# battery-board.net
KiCad netlist of a schematic drawn in EAGLE
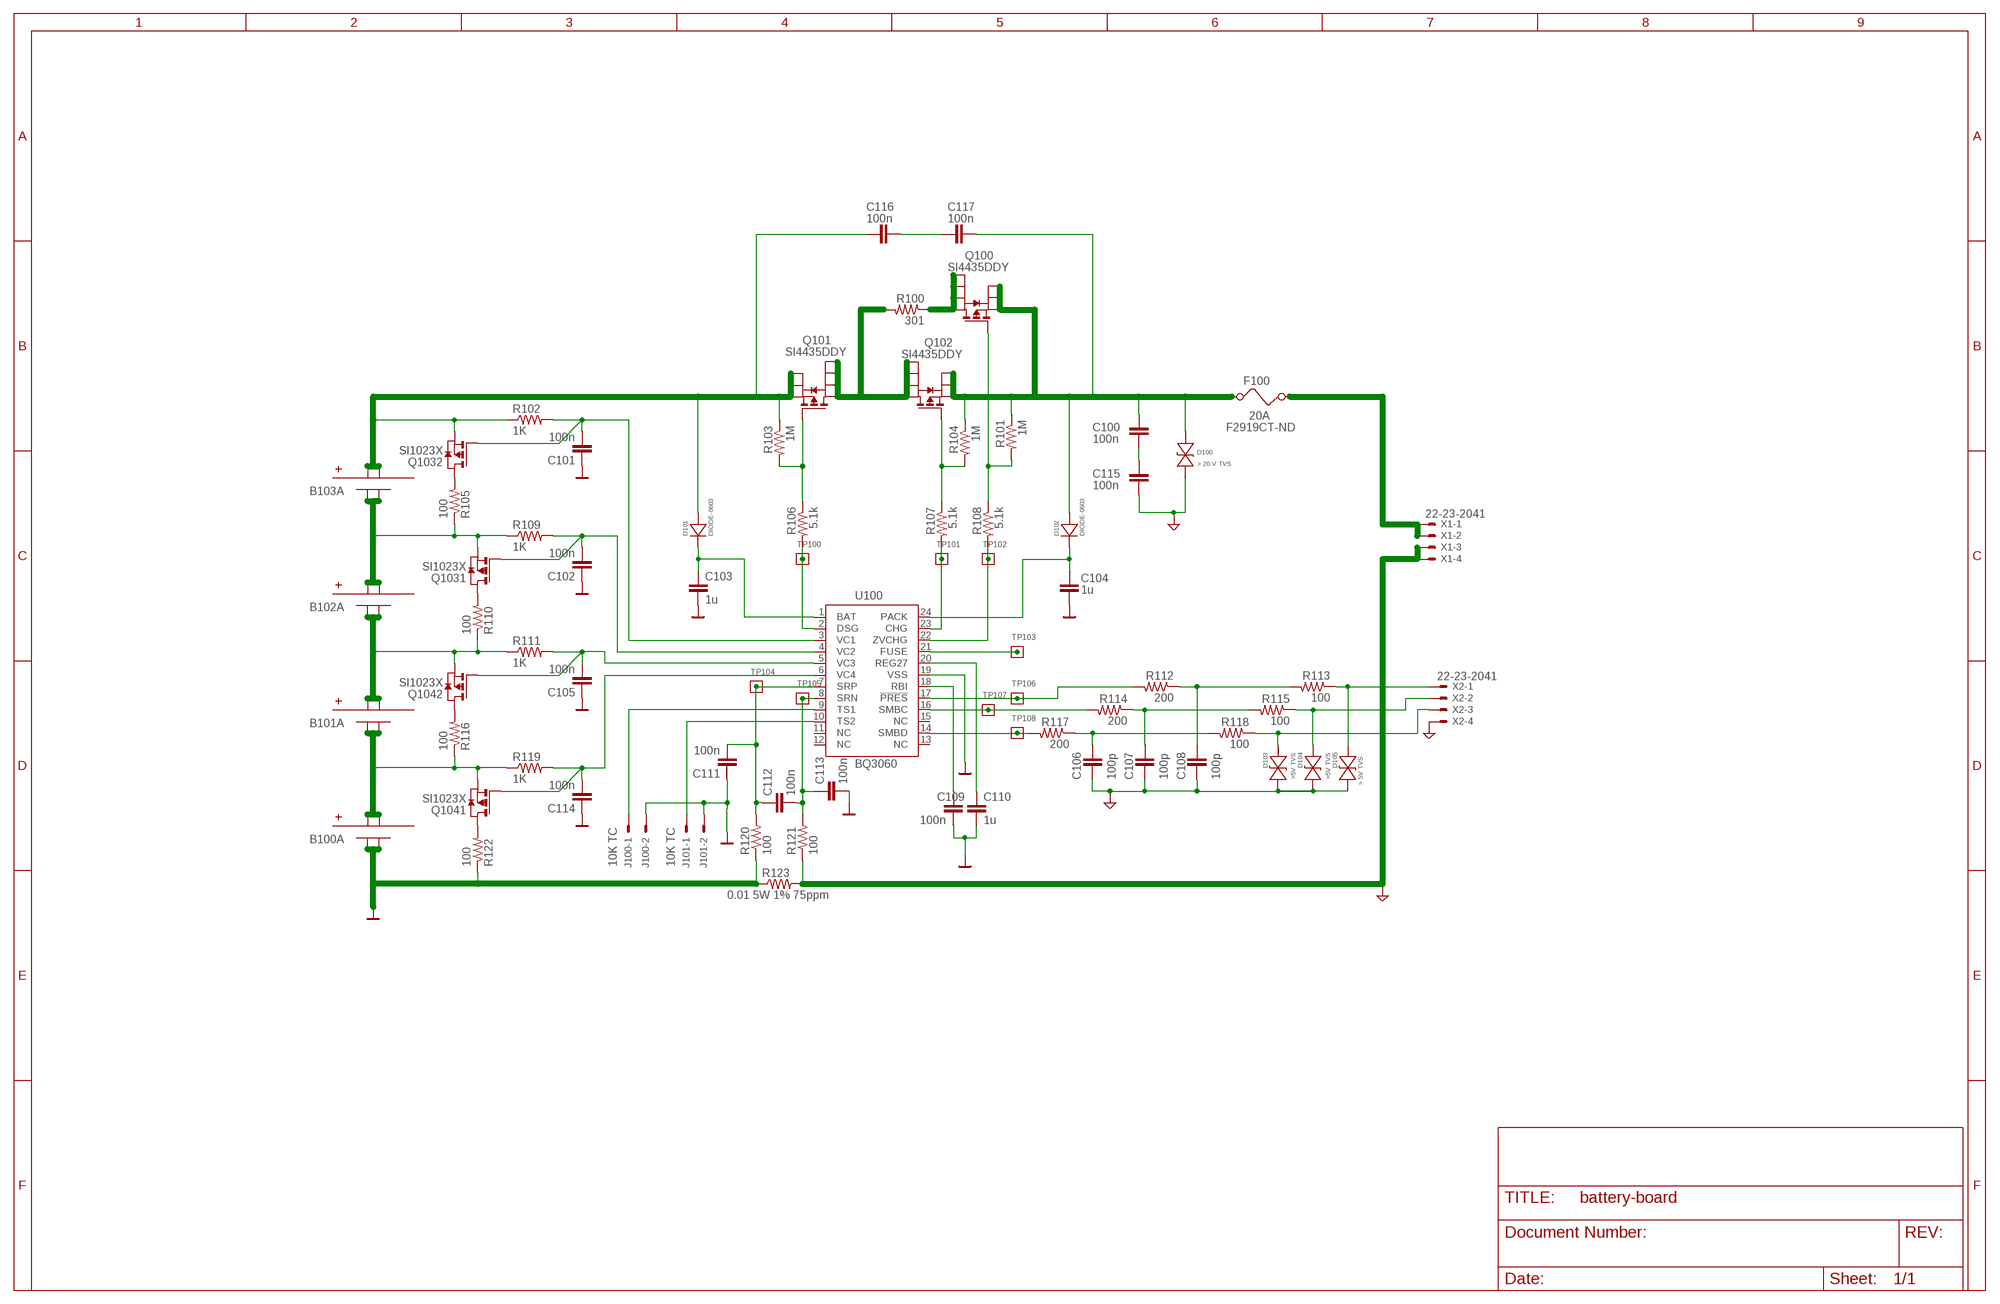
[diagram p0: schematic, sheet 1]

(export (version "E")
  (design (tool "Eeschema 10.0.6"))
  (components
    (comp (ref "B100A")
      (value "LIPO-8AHR")
      (footprint "eagle-import:LIPO-8AHR-PAC")
      (libsource (lib "eagle-import") (part "LIPO-8AHR"))
    )
    (comp (ref "B101A")
      (value "LIPO-8AHR")
      (footprint "eagle-import:LIPO-8AHR-PAC")
      (libsource (lib "eagle-import") (part "LIPO-8AHR"))
    )
    (comp (ref "B102A")
      (value "LIPO-8AHR")
      (footprint "eagle-import:LIPO-8AHR-PAC")
      (libsource (lib "eagle-import") (part "LIPO-8AHR"))
    )
    (comp (ref "B103A")
      (value "LIPO-8AHR")
      (footprint "eagle-import:LIPO-8AHR-PAC")
      (libsource (lib "eagle-import") (part "LIPO-8AHR"))
    )
    (comp (ref "C100")
      (value "100n")
      (footprint "eagle-import:0603-B-NOSILK")
      (libsource (lib "eagle-import") (part "C-EU0603-B-NOSILK"))
    )
    (comp (ref "C101")
      (value "100n")
      (footprint "eagle-import:0603-B-NOSILK")
      (libsource (lib "eagle-import") (part "C-EU0603-B-NOSILK"))
    )
    (comp (ref "C102")
      (value "100n")
      (footprint "eagle-import:0603-B-NOSILK")
      (libsource (lib "eagle-import") (part "C-EU0603-B-NOSILK"))
    )
    (comp (ref "C103")
      (value "1u")
      (footprint "eagle-import:0603-B-NOSILK")
      (libsource (lib "eagle-import") (part "C-EU0603-B-NOSILK"))
    )
    (comp (ref "C104")
      (value "1u")
      (footprint "eagle-import:0603-B-NOSILK")
      (libsource (lib "eagle-import") (part "C-EU0603-B-NOSILK"))
    )
    (comp (ref "C105")
      (value "100n")
      (footprint "eagle-import:0603-B-NOSILK")
      (libsource (lib "eagle-import") (part "C-EU0603-B-NOSILK"))
    )
    (comp (ref "C106")
      (value "100p")
      (footprint "eagle-import:0603-B-NOSILK")
      (libsource (lib "eagle-import") (part "C-EU0603-B-NOSILK"))
    )
    (comp (ref "C107")
      (value "100p")
      (footprint "eagle-import:0603-B-NOSILK")
      (libsource (lib "eagle-import") (part "C-EU0603-B-NOSILK"))
    )
    (comp (ref "C108")
      (value "100p")
      (footprint "eagle-import:0603-B-NOSILK")
      (libsource (lib "eagle-import") (part "C-EU0603-B-NOSILK"))
    )
    (comp (ref "C109")
      (value "100n")
      (footprint "eagle-import:0603-B-NOSILK")
      (libsource (lib "eagle-import") (part "C-EU0603-B-NOSILK"))
    )
    (comp (ref "C110")
      (value "1u")
      (footprint "eagle-import:0603-B-NOSILK")
      (libsource (lib "eagle-import") (part "C-EU0603-B-NOSILK"))
    )
    (comp (ref "C111")
      (value "100n")
      (footprint "eagle-import:0603-B-NOSILK")
      (libsource (lib "eagle-import") (part "C-EU0603-B-NOSILK"))
    )
    (comp (ref "C112")
      (value "100n")
      (footprint "eagle-import:0603-B-NOSILK")
      (libsource (lib "eagle-import") (part "C-EU0603-B-NOSILK"))
    )
    (comp (ref "C113")
      (value "100n")
      (footprint "eagle-import:0603-B-NOSILK")
      (libsource (lib "eagle-import") (part "C-EU0603-B-NOSILK"))
    )
    (comp (ref "C114")
      (value "100n")
      (footprint "eagle-import:0603-B-NOSILK")
      (libsource (lib "eagle-import") (part "C-EU0603-B-NOSILK"))
    )
    (comp (ref "C115")
      (value "100n")
      (footprint "eagle-import:0603-B-NOSILK")
      (libsource (lib "eagle-import") (part "C-EU0603-B-NOSILK"))
    )
    (comp (ref "C116")
      (value "100n")
      (footprint "eagle-import:0603-B-NOSILK")
      (libsource (lib "eagle-import") (part "C-EU0603-B-NOSILK"))
    )
    (comp (ref "C117")
      (value "100n")
      (footprint "eagle-import:0603-B-NOSILK")
      (libsource (lib "eagle-import") (part "C-EU0603-B-NOSILK"))
    )
    (comp (ref "D100")
      (value "> 20 V TVS")
      (footprint "eagle-import:0603-B-NOSILK-DIODE")
      (libsource (lib "eagle-import") (part "TVS-0603"))
    )
    (comp (ref "D101")
      (value "DIODE-0603")
      (footprint "eagle-import:0603-B-NOSILK-DIODE")
      (libsource (lib "eagle-import") (part "DIODE-0603"))
    )
    (comp (ref "D102")
      (value "DIODE-0603")
      (footprint "eagle-import:0603-B-NOSILK-DIODE")
      (libsource (lib "eagle-import") (part "DIODE-0603"))
    )
    (comp (ref "D103")
      (value ">5V TVS")
      (footprint "eagle-import:0603-B-NOSILK-DIODE")
      (libsource (lib "eagle-import") (part "TVS-0603"))
    )
    (comp (ref "D104")
      (value ">5V TVS")
      (footprint "eagle-import:0603-B-NOSILK-DIODE")
      (libsource (lib "eagle-import") (part "TVS-0603"))
    )
    (comp (ref "D105")
      (value "> 5V TVS")
      (footprint "eagle-import:0603-B-NOSILK-DIODE")
      (libsource (lib "eagle-import") (part "TVS-0603"))
    )
    (comp (ref "F100")
      (value "20A")
      (footprint "eagle-import:1206")
      (fields (field (name "DK") "F2919CT-ND"))
      (libsource (lib "eagle-import") (part "FUSE1206"))
    )
    (comp (ref "J100")
      (value "87758-0216")
      (footprint "eagle-import:87758-0216")
      (libsource (lib "eagle-import") (part "87758-0216"))
    )
    (comp (ref "J101")
      (value "87758-0216")
      (footprint "eagle-import:87758-0216")
      (libsource (lib "eagle-import") (part "87758-0216"))
    )
    (comp (ref "Q100")
      (value "SI4435DDY")
      (footprint "eagle-import:SO-8")
      (libsource (lib "eagle-import") (part "SI4435DDY"))
    )
    (comp (ref "Q101")
      (value "SI4435DDY")
      (footprint "eagle-import:SO-8")
      (libsource (lib "eagle-import") (part "SI4435DDY"))
    )
    (comp (ref "Q102")
      (value "SI4435DDY")
      (footprint "eagle-import:SO-8")
      (libsource (lib "eagle-import") (part "SI4435DDY"))
    )
    (comp (ref "Q103")
      (value "SI1023X")
      (footprint "eagle-import:SOT-563")
      (libsource (lib "eagle-import") (part "SI1023X"))
    )
    (comp (ref "Q104")
      (value "SI1023X")
      (footprint "eagle-import:SOT-563")
      (libsource (lib "eagle-import") (part "SI1023X"))
    )
    (comp (ref "R100")
      (value "301")
      (footprint "eagle-import:1206-B")
      (libsource (lib "eagle-import") (part "R-US_1206-B"))
    )
    (comp (ref "R101")
      (value "1M")
      (footprint "eagle-import:0603-B-NOSILK")
      (libsource (lib "eagle-import") (part "R-US_0603-B-NOSILK"))
    )
    (comp (ref "R102")
      (value "1K")
      (footprint "eagle-import:0603-B-NOSILK")
      (libsource (lib "eagle-import") (part "R-US_0603-B-NOSILK"))
    )
    (comp (ref "R103")
      (value "1M")
      (footprint "eagle-import:0603-B-NOSILK")
      (libsource (lib "eagle-import") (part "R-US_0603-B-NOSILK"))
    )
    (comp (ref "R104")
      (value "1M")
      (footprint "eagle-import:0603-B-NOSILK")
      (libsource (lib "eagle-import") (part "R-US_0603-B-NOSILK"))
    )
    (comp (ref "R105")
      (value "100")
      (footprint "eagle-import:0603-B-NOSILK")
      (libsource (lib "eagle-import") (part "R-US_0603-B-NOSILK"))
    )
    (comp (ref "R106")
      (value "5.1k")
      (footprint "eagle-import:0603-B-NOSILK")
      (libsource (lib "eagle-import") (part "R-US_0603-B-NOSILK"))
    )
    (comp (ref "R107")
      (value "5.1k")
      (footprint "eagle-import:0603-B-NOSILK")
      (libsource (lib "eagle-import") (part "R-US_0603-B-NOSILK"))
    )
    (comp (ref "R108")
      (value "5.1k")
      (footprint "eagle-import:0603-B-NOSILK")
      (libsource (lib "eagle-import") (part "R-US_0603-B-NOSILK"))
    )
    (comp (ref "R109")
      (value "1K")
      (footprint "eagle-import:0603-B-NOSILK")
      (libsource (lib "eagle-import") (part "R-US_0603-B-NOSILK"))
    )
    (comp (ref "R110")
      (value "100")
      (footprint "eagle-import:0603-B-NOSILK")
      (libsource (lib "eagle-import") (part "R-US_0603-B-NOSILK"))
    )
    (comp (ref "R111")
      (value "1K")
      (footprint "eagle-import:0603-B-NOSILK")
      (libsource (lib "eagle-import") (part "R-US_0603-B-NOSILK"))
    )
    (comp (ref "R112")
      (value "200")
      (footprint "eagle-import:0603-B-NOSILK")
      (libsource (lib "eagle-import") (part "R-US_0603-B-NOSILK"))
    )
    (comp (ref "R113")
      (value "100")
      (footprint "eagle-import:0603-B-NOSILK")
      (libsource (lib "eagle-import") (part "R-US_0603-B-NOSILK"))
    )
    (comp (ref "R114")
      (value "200")
      (footprint "eagle-import:0603-B-NOSILK")
      (libsource (lib "eagle-import") (part "R-US_0603-B-NOSILK"))
    )
    (comp (ref "R115")
      (value "100")
      (footprint "eagle-import:0603-B-NOSILK")
      (libsource (lib "eagle-import") (part "R-US_0603-B-NOSILK"))
    )
    (comp (ref "R116")
      (value "100")
      (footprint "eagle-import:0603-B-NOSILK")
      (libsource (lib "eagle-import") (part "R-US_0603-B-NOSILK"))
    )
    (comp (ref "R117")
      (value "200")
      (footprint "eagle-import:0603-B-NOSILK")
      (libsource (lib "eagle-import") (part "R-US_0603-B-NOSILK"))
    )
    (comp (ref "R118")
      (value "100")
      (footprint "eagle-import:0603-B-NOSILK")
      (libsource (lib "eagle-import") (part "R-US_0603-B-NOSILK"))
    )
    (comp (ref "R119")
      (value "1K")
      (footprint "eagle-import:0603-B-NOSILK")
      (libsource (lib "eagle-import") (part "R-US_0603-B-NOSILK"))
    )
    (comp (ref "R120")
      (value "100")
      (footprint "eagle-import:0603-B-NOSILK")
      (libsource (lib "eagle-import") (part "R-US_0603-B-NOSILK"))
    )
    (comp (ref "R121")
      (value "100")
      (footprint "eagle-import:0603-B-NOSILK")
      (libsource (lib "eagle-import") (part "R-US_0603-B-NOSILK"))
    )
    (comp (ref "R122")
      (value "100")
      (footprint "eagle-import:0603-B-NOSILK")
      (libsource (lib "eagle-import") (part "R-US_0603-B-NOSILK"))
    )
    (comp (ref "R123")
      (value "0.01 5W 1% 75ppm")
      (footprint "eagle-import:VISHAY-2818")
      (libsource (lib "eagle-import") (part "R-US-2818"))
    )
    (comp (ref "TP100")
      (value "TEST-POINT")
      (footprint "eagle-import:2MM-TEST-POINT")
      (libsource (lib "eagle-import") (part "TEST-POINT"))
    )
    (comp (ref "TP101")
      (value "TEST-POINT")
      (footprint "eagle-import:2MM-TEST-POINT")
      (libsource (lib "eagle-import") (part "TEST-POINT"))
    )
    (comp (ref "TP102")
      (value "TEST-POINT")
      (footprint "eagle-import:2MM-TEST-POINT")
      (libsource (lib "eagle-import") (part "TEST-POINT"))
    )
    (comp (ref "TP103")
      (value "TEST-POINT")
      (footprint "eagle-import:2MM-TEST-POINT")
      (libsource (lib "eagle-import") (part "TEST-POINT"))
    )
    (comp (ref "TP104")
      (value "TEST-POINT")
      (footprint "eagle-import:2MM-TEST-POINT")
      (libsource (lib "eagle-import") (part "TEST-POINT"))
    )
    (comp (ref "TP105")
      (value "TEST-POINT")
      (footprint "eagle-import:2MM-TEST-POINT")
      (libsource (lib "eagle-import") (part "TEST-POINT"))
    )
    (comp (ref "TP106")
      (value "TEST-POINT")
      (footprint "eagle-import:2MM-TEST-POINT")
      (libsource (lib "eagle-import") (part "TEST-POINT"))
    )
    (comp (ref "TP107")
      (value "TEST-POINT")
      (footprint "eagle-import:2MM-TEST-POINT")
      (libsource (lib "eagle-import") (part "TEST-POINT"))
    )
    (comp (ref "TP108")
      (value "TEST-POINT")
      (footprint "eagle-import:2MM-TEST-POINT")
      (libsource (lib "eagle-import") (part "TEST-POINT"))
    )
    (comp (ref "U100")
      (value "BQ3060PW")
      (footprint "eagle-import:PW-R-PDSO-G24")
      (libsource (lib "eagle-import") (part "BQ3060PW"))
    )
    (comp (ref "X1")
      (value "22-23-2041")
      (footprint "eagle-import:22-23-2041")
      (fields (field (name "MF") "MOLEX"))
      (libsource (lib "eagle-import") (part "22-23-2041"))
    )
    (comp (ref "X2")
      (value "22-23-2041")
      (footprint "eagle-import:22-23-2041")
      (fields (field (name "MF") "MOLEX"))
      (libsource (lib "eagle-import") (part "22-23-2041"))
    )
  )
  (nets
    (net (code "1") (name "Net-(C100-Pad1)") (class "Default")
      (node (ref "C100") (pin "1") (pinfunction "1_1") (pintype "passive"))
      (node (ref "C117") (pin "2") (pinfunction "2_2") (pintype "passive"))
      (node (ref "D100") (pin "ANODE") (pinfunction "ANODE_ANODE") (pintype "passive"))
      (node (ref "D102") (pin "ANODE") (pinfunction "ANODE_ANODE") (pintype "passive"))
      (node (ref "F100") (pin "1") (pinfunction "1_1") (pintype "passive"))
      (node (ref "Q100") (pin "1") (pinfunction "S_1") (pintype "passive"))
      (node (ref "Q100") (pin "2") (pinfunction "S_2") (pintype "passive"))
      (node (ref "Q100") (pin "3") (pinfunction "S_3") (pintype "passive"))
      (node (ref "Q102") (pin "1") (pinfunction "S_1") (pintype "passive"))
      (node (ref "Q102") (pin "2") (pinfunction "S_2") (pintype "passive"))
      (node (ref "Q102") (pin "3") (pinfunction "S_3") (pintype "passive"))
      (node (ref "R101") (pin "1") (pinfunction "1_1") (pintype "passive"))
      (node (ref "R104") (pin "1") (pinfunction "1_1") (pintype "passive"))
    )
    (net (code "2") (name "Net-(C100-Pad2)") (class "Default")
      (node (ref "C100") (pin "2") (pinfunction "2_2") (pintype "passive"))
      (node (ref "C115") (pin "1") (pinfunction "1_1") (pintype "passive"))
    )
    (net (code "3") (name "Net-(C106-Pad1)") (class "Default")
      (node (ref "C106") (pin "1") (pinfunction "1_1") (pintype "passive"))
      (node (ref "R117") (pin "1") (pinfunction "1_1") (pintype "passive"))
      (node (ref "R118") (pin "2") (pinfunction "2_2") (pintype "passive"))
    )
    (net (code "4") (name "Net-(C107-Pad1)") (class "Default")
      (node (ref "C107") (pin "1") (pinfunction "1_1") (pintype "passive"))
      (node (ref "R114") (pin "1") (pinfunction "1_1") (pintype "passive"))
      (node (ref "R115") (pin "2") (pinfunction "2_2") (pintype "passive"))
    )
    (net (code "5") (name "Net-(C108-Pad1)") (class "Default")
      (node (ref "C108") (pin "1") (pinfunction "1_1") (pintype "passive"))
      (node (ref "R112") (pin "1") (pinfunction "1_1") (pintype "passive"))
      (node (ref "R113") (pin "2") (pinfunction "2_2") (pintype "passive"))
    )
    (net (code "6") (name "Net-(C116-Pad2)") (class "Default")
      (node (ref "C116") (pin "2") (pinfunction "2_2") (pintype "passive"))
      (node (ref "C117") (pin "1") (pinfunction "1_1") (pintype "passive"))
    )
    (net (code "7") (name "Net-(J100A-S)") (class "Default")
      (node (ref "J100") (pin "1") (pinfunction "S_1") (pintype "passive"))
      (node (ref "U100") (pin "9") (pinfunction "TS1_9") (pintype "input"))
    )
    (net (code "8") (name "Net-(J101A-S)") (class "Default")
      (node (ref "J101") (pin "1") (pinfunction "S_1") (pintype "passive"))
      (node (ref "U100") (pin "10") (pinfunction "TS2_10") (pintype "input"))
    )
    (net (code "9") (name "Net-(Q100-D-Pad5)") (class "Default")
      (node (ref "Q100") (pin "5") (pinfunction "D_5") (pintype "passive"))
      (node (ref "Q100") (pin "6") (pinfunction "D_6") (pintype "passive"))
      (node (ref "Q100") (pin "7") (pinfunction "D_7") (pintype "passive"))
      (node (ref "Q100") (pin "8") (pinfunction "D_8") (pintype "passive"))
      (node (ref "R100") (pin "1") (pinfunction "1_1") (pintype "passive"))
    )
    (net (code "10") (name "Net-(Q100-G)") (class "Default")
      (node (ref "Q100") (pin "4") (pinfunction "G_4") (pintype "passive"))
      (node (ref "R101") (pin "2") (pinfunction "2_2") (pintype "passive"))
      (node (ref "R108") (pin "1") (pinfunction "1_1") (pintype "passive"))
    )
    (net (code "11") (name "Net-(Q101-D-Pad5)") (class "Default")
      (node (ref "Q101") (pin "5") (pinfunction "D_5") (pintype "passive"))
      (node (ref "Q101") (pin "6") (pinfunction "D_6") (pintype "passive"))
      (node (ref "Q101") (pin "7") (pinfunction "D_7") (pintype "passive"))
      (node (ref "Q101") (pin "8") (pinfunction "D_8") (pintype "passive"))
      (node (ref "Q102") (pin "5") (pinfunction "D_5") (pintype "passive"))
      (node (ref "Q102") (pin "6") (pinfunction "D_6") (pintype "passive"))
      (node (ref "Q102") (pin "7") (pinfunction "D_7") (pintype "passive"))
      (node (ref "Q102") (pin "8") (pinfunction "D_8") (pintype "passive"))
      (node (ref "R100") (pin "2") (pinfunction "2_2") (pintype "passive"))
    )
    (net (code "12") (name "Net-(Q101-G)") (class "Default")
      (node (ref "Q101") (pin "4") (pinfunction "G_4") (pintype "passive"))
      (node (ref "R103") (pin "2") (pinfunction "2_2") (pintype "passive"))
      (node (ref "R106") (pin "1") (pinfunction "1_1") (pintype "passive"))
    )
    (net (code "13") (name "Net-(Q102-G)") (class "Default")
      (node (ref "Q102") (pin "4") (pinfunction "G_4") (pintype "passive"))
      (node (ref "R104") (pin "2") (pinfunction "2_2") (pintype "passive"))
      (node (ref "R107") (pin "1") (pinfunction "1_1") (pintype "passive"))
    )
    (net (code "14") (name "Net-(Q103A-D)") (class "Default")
      (node (ref "Q103") (pin "6") (pinfunction "D_6") (pintype "passive"))
      (node (ref "R110") (pin "2") (pinfunction "2_2") (pintype "passive"))
    )
    (net (code "15") (name "Net-(Q103A-G)") (class "Default")
      (node (ref "C102") (pin "2") (pinfunction "2_2") (pintype "passive"))
      (node (ref "Q103") (pin "2") (pinfunction "G_2") (pintype "passive"))
      (node (ref "R109") (pin "2") (pinfunction "2_2") (pintype "passive"))
      (node (ref "U100") (pin "4") (pinfunction "VC2_4") (pintype "input"))
    )
    (net (code "16") (name "Net-(Q103A-S)") (class "Default")
      (node (ref "B102A") (pin "B+@1") (pinfunction "B+_B+@1") (pintype "passive"))
      (node (ref "B102A") (pin "B+@2") (pinfunction "B+_B+@2") (pintype "passive"))
      (node (ref "B103A") (pin "B-@1") (pinfunction "B-_B-@1") (pintype "passive"))
      (node (ref "B103A") (pin "B-@2") (pinfunction "B-_B-@2") (pintype "passive"))
      (node (ref "Q103") (pin "1") (pinfunction "S_1") (pintype "passive"))
      (node (ref "R105") (pin "1") (pinfunction "1_1") (pintype "passive"))
      (node (ref "R109") (pin "1") (pinfunction "1_1") (pintype "passive"))
    )
    (net (code "17") (name "Net-(Q103B-D)") (class "Default")
      (node (ref "Q103") (pin "3") (pinfunction "D_3") (pintype "passive"))
      (node (ref "R105") (pin "2") (pinfunction "2_2") (pintype "passive"))
    )
    (net (code "18") (name "Net-(Q103B-G)") (class "Default")
      (node (ref "C101") (pin "2") (pinfunction "2_2") (pintype "passive"))
      (node (ref "Q103") (pin "5") (pinfunction "G_5") (pintype "passive"))
      (node (ref "R102") (pin "2") (pinfunction "2_2") (pintype "passive"))
      (node (ref "U100") (pin "3") (pinfunction "VC1_3") (pintype "input"))
    )
    (net (code "19") (name "Net-(Q103B-S)") (class "Default")
      (node (ref "B103A") (pin "B+@1") (pinfunction "B+_B+@1") (pintype "passive"))
      (node (ref "B103A") (pin "B+@2") (pinfunction "B+_B+@2") (pintype "passive"))
      (node (ref "C116") (pin "1") (pinfunction "1_1") (pintype "passive"))
      (node (ref "D101") (pin "ANODE") (pinfunction "ANODE_ANODE") (pintype "passive"))
      (node (ref "Q101") (pin "1") (pinfunction "S_1") (pintype "passive"))
      (node (ref "Q101") (pin "2") (pinfunction "S_2") (pintype "passive"))
      (node (ref "Q101") (pin "3") (pinfunction "S_3") (pintype "passive"))
      (node (ref "Q103") (pin "4") (pinfunction "S_4") (pintype "passive"))
      (node (ref "R102") (pin "1") (pinfunction "1_1") (pintype "passive"))
      (node (ref "R103") (pin "1") (pinfunction "1_1") (pintype "passive"))
    )
    (net (code "20") (name "Net-(Q104A-D)") (class "Default")
      (node (ref "Q104") (pin "6") (pinfunction "D_6") (pintype "passive"))
      (node (ref "R122") (pin "2") (pinfunction "2_2") (pintype "passive"))
    )
    (net (code "21") (name "Net-(Q104A-G)") (class "Default")
      (node (ref "C114") (pin "2") (pinfunction "2_2") (pintype "passive"))
      (node (ref "Q104") (pin "2") (pinfunction "G_2") (pintype "passive"))
      (node (ref "R119") (pin "2") (pinfunction "2_2") (pintype "passive"))
      (node (ref "U100") (pin "6") (pinfunction "VC4_6") (pintype "input"))
    )
    (net (code "22") (name "Net-(Q104A-S)") (class "Default")
      (node (ref "B100A") (pin "B+@1") (pinfunction "B+_B+@1") (pintype "passive"))
      (node (ref "B100A") (pin "B+@2") (pinfunction "B+_B+@2") (pintype "passive"))
      (node (ref "B101A") (pin "B-@1") (pinfunction "B-_B-@1") (pintype "passive"))
      (node (ref "B101A") (pin "B-@2") (pinfunction "B-_B-@2") (pintype "passive"))
      (node (ref "Q104") (pin "1") (pinfunction "S_1") (pintype "passive"))
      (node (ref "R116") (pin "1") (pinfunction "1_1") (pintype "passive"))
      (node (ref "R119") (pin "1") (pinfunction "1_1") (pintype "passive"))
    )
    (net (code "23") (name "Net-(Q104B-D)") (class "Default")
      (node (ref "Q104") (pin "3") (pinfunction "D_3") (pintype "passive"))
      (node (ref "R116") (pin "2") (pinfunction "2_2") (pintype "passive"))
    )
    (net (code "24") (name "Net-(Q104B-G)") (class "Default")
      (node (ref "C105") (pin "2") (pinfunction "2_2") (pintype "passive"))
      (node (ref "Q104") (pin "5") (pinfunction "G_5") (pintype "passive"))
      (node (ref "R111") (pin "2") (pinfunction "2_2") (pintype "passive"))
      (node (ref "U100") (pin "5") (pinfunction "VC3_5") (pintype "input"))
    )
    (net (code "25") (name "Net-(Q104B-S)") (class "Default")
      (node (ref "B101A") (pin "B+@1") (pinfunction "B+_B+@1") (pintype "passive"))
      (node (ref "B101A") (pin "B+@2") (pinfunction "B+_B+@2") (pintype "passive"))
      (node (ref "B102A") (pin "B-@1") (pinfunction "B-_B-@1") (pintype "passive"))
      (node (ref "B102A") (pin "B-@2") (pinfunction "B-_B-@2") (pintype "passive"))
      (node (ref "Q104") (pin "4") (pinfunction "S_4") (pintype "passive"))
      (node (ref "R110") (pin "1") (pinfunction "1_1") (pintype "passive"))
      (node (ref "R111") (pin "1") (pinfunction "1_1") (pintype "passive"))
    )
    (net (code "26") (name "Net-(TP100-P$1)") (class "Default")
      (node (ref "R106") (pin "2") (pinfunction "2_2") (pintype "passive"))
      (node (ref "TP100") (pin "1") (pinfunction "P$1_1") (pintype "passive"))
      (node (ref "U100") (pin "2") (pinfunction "DSG_2") (pintype "output"))
    )
    (net (code "27") (name "Net-(TP101-P$1)") (class "Default")
      (node (ref "R107") (pin "2") (pinfunction "2_2") (pintype "passive"))
      (node (ref "TP101") (pin "1") (pinfunction "P$1_1") (pintype "passive"))
      (node (ref "U100") (pin "23") (pinfunction "CHG_23") (pintype "output"))
    )
    (net (code "28") (name "Net-(TP102-P$1)") (class "Default")
      (node (ref "R108") (pin "2") (pinfunction "2_2") (pintype "passive"))
      (node (ref "TP102") (pin "1") (pinfunction "P$1_1") (pintype "passive"))
      (node (ref "U100") (pin "22") (pinfunction "ZVCHG_22") (pintype "output"))
    )
    (net (code "29") (name "Net-(TP103-P$1)") (class "Default")
      (node (ref "TP103") (pin "1") (pinfunction "P$1_1") (pintype "passive"))
      (node (ref "U100") (pin "21") (pinfunction "FUSE_21") (pintype "bidirectional"))
    )
    (net (code "30") (name "Net-(TP104-P$1)") (class "Default")
      (node (ref "C111") (pin "2") (pinfunction "2_2") (pintype "passive"))
      (node (ref "C112") (pin "1") (pinfunction "1_1") (pintype "passive"))
      (node (ref "R120") (pin "2") (pinfunction "2_2") (pintype "passive"))
      (node (ref "TP104") (pin "1") (pinfunction "P$1_1") (pintype "passive"))
      (node (ref "U100") (pin "7") (pinfunction "SRP_7") (pintype "input"))
    )
    (net (code "31") (name "Net-(TP105-P$1)") (class "Default")
      (node (ref "C112") (pin "2") (pinfunction "2_2") (pintype "passive"))
      (node (ref "C113") (pin "1") (pinfunction "1_1") (pintype "passive"))
      (node (ref "R121") (pin "2") (pinfunction "2_2") (pintype "passive"))
      (node (ref "TP105") (pin "1") (pinfunction "P$1_1") (pintype "passive"))
      (node (ref "U100") (pin "8") (pinfunction "SRN_8") (pintype "input"))
    )
    (net (code "32") (name "Net-(TP106-P$1)") (class "Default")
      (node (ref "R112") (pin "2") (pinfunction "2_2") (pintype "passive"))
      (node (ref "TP106") (pin "1") (pinfunction "P$1_1") (pintype "passive"))
      (node (ref "U100") (pin "17") (pinfunction "~{PRES}_17") (pintype "input"))
    )
    (net (code "33") (name "Net-(TP107-P$1)") (class "Default")
      (node (ref "R114") (pin "2") (pinfunction "2_2") (pintype "passive"))
      (node (ref "TP107") (pin "1") (pinfunction "P$1_1") (pintype "passive"))
      (node (ref "U100") (pin "16") (pinfunction "SMBC_16") (pintype "bidirectional"))
    )
    (net (code "34") (name "Net-(TP108-P$1)") (class "Default")
      (node (ref "R117") (pin "2") (pinfunction "2_2") (pintype "passive"))
      (node (ref "TP108") (pin "1") (pinfunction "P$1_1") (pintype "passive"))
      (node (ref "U100") (pin "14") (pinfunction "SMBD_14") (pintype "bidirectional"))
    )
    (net (code "35") (name "Net-(U100-BAT)") (class "Default")
      (node (ref "C103") (pin "1") (pinfunction "1_1") (pintype "passive"))
      (node (ref "D101") (pin "CATHODE") (pinfunction "CATHODE_CATHODE") (pintype "passive"))
      (node (ref "U100") (pin "1") (pinfunction "BAT_1") (pintype "power_in"))
    )
    (net (code "36") (name "Net-(U100-PACK)") (class "Default")
      (node (ref "C104") (pin "1") (pinfunction "1_1") (pintype "passive"))
      (node (ref "D102") (pin "CATHODE") (pinfunction "CATHODE_CATHODE") (pintype "passive"))
      (node (ref "U100") (pin "24") (pinfunction "PACK_24") (pintype "power_in"))
    )
    (net (code "37") (name "Net-(U100-RBI)") (class "Default")
      (node (ref "C109") (pin "1") (pinfunction "1_1") (pintype "passive"))
      (node (ref "U100") (pin "18") (pinfunction "RBI_18") (pintype "power_in"))
    )
    (net (code "38") (name "Net-(U100-REG27)") (class "Default")
      (node (ref "C110") (pin "1") (pinfunction "1_1") (pintype "passive"))
      (node (ref "U100") (pin "20") (pinfunction "REG27_20") (pintype "power_in"))
    )
    (net (code "39") (name "Net-(X1A-S)") (class "Default")
      (node (ref "F100") (pin "2") (pinfunction "2_2") (pintype "passive"))
      (node (ref "X1") (pin "1") (pinfunction "S_1") (pintype "passive"))
      (node (ref "X1") (pin "2") (pinfunction "S_2") (pintype "passive"))
    )
    (net (code "40") (name "Net-(X2A-S)") (class "Default")
      (node (ref "D105") (pin "ANODE") (pinfunction "ANODE_ANODE") (pintype "passive"))
      (node (ref "R113") (pin "1") (pinfunction "1_1") (pintype "passive"))
      (node (ref "X2") (pin "1") (pinfunction "S_1") (pintype "passive"))
    )
    (net (code "41") (name "Net-(X2B-S)") (class "Default")
      (node (ref "D104") (pin "ANODE") (pinfunction "ANODE_ANODE") (pintype "passive"))
      (node (ref "R115") (pin "1") (pinfunction "1_1") (pintype "passive"))
      (node (ref "X2") (pin "2") (pinfunction "S_2") (pintype "passive"))
    )
    (net (code "42") (name "Net-(X2C-S)") (class "Default")
      (node (ref "D103") (pin "ANODE") (pinfunction "ANODE_ANODE") (pintype "passive"))
      (node (ref "R118") (pin "1") (pinfunction "1_1") (pintype "passive"))
      (node (ref "X2") (pin "3") (pinfunction "S_3") (pintype "passive"))
    )
    (net (code "43") (name "SUP_GND_BAR") (class "Default")
      (node (ref "B100A") (pin "B-@1") (pinfunction "B-_B-@1") (pintype "passive"))
      (node (ref "B100A") (pin "B-@2") (pinfunction "B-_B-@2") (pintype "passive"))
      (node (ref "C101") (pin "1") (pinfunction "1_1") (pintype "passive"))
      (node (ref "C102") (pin "1") (pinfunction "1_1") (pintype "passive"))
      (node (ref "C103") (pin "2") (pinfunction "2_2") (pintype "passive"))
      (node (ref "C104") (pin "2") (pinfunction "2_2") (pintype "passive"))
      (node (ref "C105") (pin "1") (pinfunction "1_1") (pintype "passive"))
      (node (ref "C109") (pin "2") (pinfunction "2_2") (pintype "passive"))
      (node (ref "C110") (pin "2") (pinfunction "2_2") (pintype "passive"))
      (node (ref "C111") (pin "1") (pinfunction "1_1") (pintype "passive"))
      (node (ref "C113") (pin "2") (pinfunction "2_2") (pintype "passive"))
      (node (ref "C114") (pin "1") (pinfunction "1_1") (pintype "passive"))
      (node (ref "J100") (pin "2") (pinfunction "S_2") (pintype "passive"))
      (node (ref "J101") (pin "2") (pinfunction "S_2") (pintype "passive"))
      (node (ref "R120") (pin "1") (pinfunction "1_1") (pintype "passive"))
      (node (ref "R122") (pin "1") (pinfunction "1_1") (pintype "passive"))
      (node (ref "R123") (pin "P$1") (pinfunction "1_P$1") (pintype "passive"))
      (node (ref "U100") (pin "19") (pinfunction "VSS_19") (pintype "power_in"))
    )
    (net (code "44") (name "SUP_GND_TRIANGLE") (class "Default")
      (node (ref "C106") (pin "2") (pinfunction "2_2") (pintype "passive"))
      (node (ref "C107") (pin "2") (pinfunction "2_2") (pintype "passive"))
      (node (ref "C108") (pin "2") (pinfunction "2_2") (pintype "passive"))
      (node (ref "C115") (pin "2") (pinfunction "2_2") (pintype "passive"))
      (node (ref "D100") (pin "CATHODE") (pinfunction "CATHODE_CATHODE") (pintype "passive"))
      (node (ref "D103") (pin "CATHODE") (pinfunction "CATHODE_CATHODE") (pintype "passive"))
      (node (ref "D104") (pin "CATHODE") (pinfunction "CATHODE_CATHODE") (pintype "passive"))
      (node (ref "D105") (pin "CATHODE") (pinfunction "CATHODE_CATHODE") (pintype "passive"))
      (node (ref "R121") (pin "1") (pinfunction "1_1") (pintype "passive"))
      (node (ref "R123") (pin "P$2") (pinfunction "2_P$2") (pintype "passive"))
      (node (ref "X1") (pin "3") (pinfunction "S_3") (pintype "passive"))
      (node (ref "X1") (pin "4") (pinfunction "S_4") (pintype "passive"))
      (node (ref "X2") (pin "4") (pinfunction "S_4") (pintype "passive"))
    )
    (net (code "45") (name "unconnected-(U100-NC-Pad11)") (class "Default")
      (node (ref "U100") (pin "11") (pinfunction "NC_11") (pintype "no_connect"))
    )
    (net (code "46") (name "unconnected-(U100-NC-Pad12)") (class "Default")
      (node (ref "U100") (pin "12") (pinfunction "NC_12") (pintype "no_connect"))
    )
    (net (code "47") (name "unconnected-(U100-NC-Pad13)") (class "Default")
      (node (ref "U100") (pin "13") (pinfunction "NC_13") (pintype "no_connect"))
    )
    (net (code "48") (name "unconnected-(U100-NC-Pad15)") (class "Default")
      (node (ref "U100") (pin "15") (pinfunction "NC_15") (pintype "no_connect"))
    )
  )
)
